# OPA_T12.net
KiCad netlist of a schematic drawn in Altium Designer
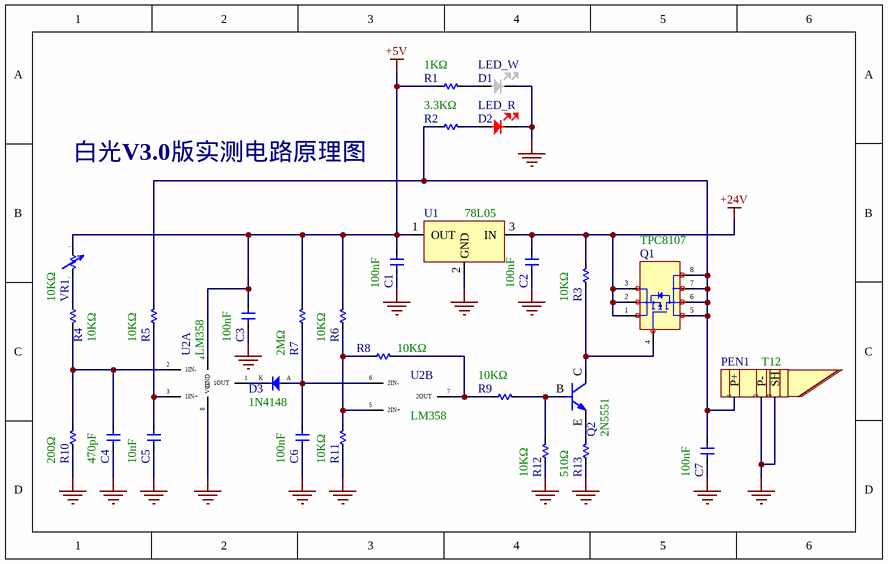
[diagram p0: OPA_T12.SchDoc]

(export (version "E")
  (design (tool "Eeschema 10.0.6"))
  (components
    (comp (ref "C1") (value "100nF") (description "贴片电容") (libsource (lib "SCHLIB_2022") (part "CAP NP")))
    (comp (ref "C2") (value "100nF") (description "贴片电容") (libsource (lib "SCHLIB_2022") (part "CAP NP")))
    (comp (ref "C3") (value "100nF") (description "贴片电容") (libsource (lib "SCHLIB_2022") (part "CAP NP")))
    (comp (ref "C4") (value "470pF") (description "贴片电容") (libsource (lib "SCHLIB_2022") (part "CAP NP")))
    (comp (ref "C5") (value "10nF") (description "贴片电容") (libsource (lib "SCHLIB_2022") (part "CAP NP")))
    (comp (ref "C6") (value "100nF") (description "贴片电容") (libsource (lib "SCHLIB_2022") (part "CAP NP")))
    (comp (ref "C7") (value "100nF") (description "贴片电容") (libsource (lib "SCHLIB_2022") (part "CAP NP")))
    (comp (ref "D1") (value "LED_W") (description "白色发光二极管") (libsource (lib "SCHLIB_2022") (part "LED_W")))
    (comp (ref "D2") (value "LED_R") (description "红色发光二极管") (libsource (lib "SCHLIB_2022") (part "LED_R")))
    (comp (ref "D3") (value "1N4148") (libsource (lib "SCHLIB_2022") (part "DIODE")))
    (comp (ref "PEN1") (value "T12") (footprint "T13") (libsource (lib "SCHLIB_2022") (part "IRON_PEN")))
    (comp (ref "Q1")
      (value "TPC8107")
      (footprint "SO-8M")
      (description "P沟道 40V 10A")
      (libsource (lib "SCHLIB_2022") (part "AO4485"))
    )
    (comp (ref "Q2") (value "2N5551") (libsource (lib "SCHLIB_2022") (part "NPN BCE")))
    (comp (ref "R1") (value "1KΩ") (description "贴片电阻") (libsource (lib "SCHLIB_2022") (part "ResSemi")))
    (comp (ref "R2") (value "3.3KΩ") (description "贴片电阻") (libsource (lib "SCHLIB_2022") (part "ResSemi")))
    (comp (ref "R3") (value "10KΩ") (description "贴片电阻") (libsource (lib "SCHLIB_2022") (part "ResSemi")))
    (comp (ref "R4") (value "10KΩ") (description "贴片电阻") (libsource (lib "SCHLIB_2022") (part "ResSemi")))
    (comp (ref "R5") (value "10KΩ") (description "贴片电阻") (libsource (lib "SCHLIB_2022") (part "ResSemi")))
    (comp (ref "R6") (value "10KΩ") (description "贴片电阻") (libsource (lib "SCHLIB_2022") (part "ResSemi")))
    (comp (ref "R7") (value "2MΩ") (description "贴片电阻") (libsource (lib "SCHLIB_2022") (part "ResSemi")))
    (comp (ref "R8") (value "10KΩ") (description "贴片电阻") (libsource (lib "SCHLIB_2022") (part "ResSemi")))
    (comp (ref "R9") (value "10KΩ") (description "贴片电阻") (libsource (lib "SCHLIB_2022") (part "ResSemi")))
    (comp (ref "R10") (value "200Ω") (description "贴片电阻") (libsource (lib "SCHLIB_2022") (part "ResSemi")))
    (comp (ref "R11") (value "10KΩ") (description "贴片电阻") (libsource (lib "SCHLIB_2022") (part "ResSemi")))
    (comp (ref "R12") (value "10KΩ") (description "贴片电阻") (libsource (lib "SCHLIB_2022") (part "ResSemi")))
    (comp (ref "R13") (value "510Ω") (description "贴片电阻") (libsource (lib "SCHLIB_2022") (part "ResSemi")))
    (comp (ref "U1")
      (value "78L05")
      (footprint "SOT-89")
      (description "5V线性稳压芯片")
      (libsource (lib "SCHLIB_2022") (part "78L05"))
    )
    (comp (ref "U2") (value "LM358") (footprint "SO-8") (libsource (lib "SCHLIB_2022") (part "LM393")))
    (comp (ref "VR1") (value "10KΩ") (libsource (lib "SCHLIB_2022") (part "ResSemi_5")))
  )
  (nets
    (net (code "1") (name "+5V") (class "Default")
      (node (ref "C1") (pin "1") (pinfunction "1_1") (pintype "passive"))
      (node (ref "C3") (pin "1") (pinfunction "1_1") (pintype "passive"))
      (node (ref "R1") (pin "1") (pinfunction "1_1") (pintype "passive"))
      (node (ref "R6") (pin "2") (pinfunction "2_2") (pintype "passive"))
      (node (ref "R7") (pin "2") (pinfunction "2_2") (pintype "passive"))
      (node (ref "U1") (pin "1") (pinfunction "OUT_1") (pintype "passive"))
      (node (ref "U2") (pin "4") (pinfunction "GND_4") (pintype "passive"))
      (node (ref "VR1") (pin "1") (pinfunction "1_1") (pintype "passive"))
    )
    (net (code "2") (name "+24V") (class "Default")
      (node (ref "C2") (pin "1") (pinfunction "1_1") (pintype "passive"))
      (node (ref "Q1") (pin "1") (pinfunction "S_1") (pintype "passive"))
      (node (ref "Q1") (pin "2") (pinfunction "S_2") (pintype "passive"))
      (node (ref "Q1") (pin "3") (pinfunction "S_3") (pintype "passive"))
      (node (ref "R3") (pin "2") (pinfunction "2_2") (pintype "passive"))
      (node (ref "U1") (pin "3") (pinfunction "IN_3") (pintype "passive"))
    )
    (net (code "3") (name "GND") (class "Default")
      (node (ref "C1") (pin "2") (pinfunction "2_2") (pintype "passive"))
      (node (ref "C2") (pin "2") (pinfunction "2_2") (pintype "passive"))
      (node (ref "C3") (pin "2") (pinfunction "2_2") (pintype "passive"))
      (node (ref "C4") (pin "2") (pinfunction "2_2") (pintype "passive"))
      (node (ref "C5") (pin "2") (pinfunction "2_2") (pintype "passive"))
      (node (ref "C6") (pin "2") (pinfunction "2_2") (pintype "passive"))
      (node (ref "C7") (pin "2") (pinfunction "2_2") (pintype "passive"))
      (node (ref "D1") (pin "C") (pinfunction "CATHODE_C") (pintype "passive"))
      (node (ref "D2") (pin "C") (pinfunction "CATHODE_C") (pintype "passive"))
      (node (ref "PEN1") (pin "2") (pinfunction "P-_2") (pintype "passive"))
      (node (ref "PEN1") (pin "3") (pinfunction "SH_3") (pintype "passive"))
      (node (ref "R10") (pin "1") (pinfunction "1_1") (pintype "passive"))
      (node (ref "R11") (pin "1") (pinfunction "1_1") (pintype "passive"))
      (node (ref "R12") (pin "1") (pinfunction "1_1") (pintype "passive"))
      (node (ref "R13") (pin "1") (pinfunction "1_1") (pintype "passive"))
      (node (ref "U1") (pin "2") (pinfunction "GND_2") (pintype "passive"))
      (node (ref "U2") (pin "8") (pinfunction "VCC_8") (pintype "passive"))
    )
    (net (code "4") (name "Net-(D1-ANODE)") (class "Default")
      (node (ref "D1") (pin "A") (pinfunction "ANODE_A") (pintype "passive"))
      (node (ref "R1") (pin "2") (pinfunction "2_2") (pintype "passive"))
    )
    (net (code "5") (name "Net-(D2-ANODE)") (class "Default")
      (node (ref "D2") (pin "A") (pinfunction "ANODE_A") (pintype "passive"))
      (node (ref "R2") (pin "2") (pinfunction "2_2") (pintype "passive"))
    )
    (net (code "6") (name "Net-(D3-ANODE)") (class "Default")
      (node (ref "C6") (pin "1") (pinfunction "1_1") (pintype "passive"))
      (node (ref "D3") (pin "A") (pinfunction "ANODE_A") (pintype "passive"))
      (node (ref "R7") (pin "1") (pinfunction "1_1") (pintype "passive"))
      (node (ref "U2") (pin "6") (pinfunction "2IN-_6") (pintype "passive"))
    )
    (net (code "7") (name "Net-(D3-CATHODE)") (class "Default")
      (node (ref "D3") (pin "K") (pinfunction "CATHODE_K") (pintype "passive"))
      (node (ref "U2") (pin "1") (pinfunction "1OUT_1") (pintype "passive"))
    )
    (net (code "8") (name "Net-(PEN1-P+)") (class "Default")
      (node (ref "C7") (pin "1") (pinfunction "1_1") (pintype "passive"))
      (node (ref "PEN1") (pin "1") (pinfunction "P+_1") (pintype "passive"))
      (node (ref "Q1") (pin "5") (pinfunction "D_5") (pintype "passive"))
      (node (ref "Q1") (pin "6") (pinfunction "D_6") (pintype "passive"))
      (node (ref "Q1") (pin "7") (pinfunction "D_7") (pintype "passive"))
      (node (ref "Q1") (pin "8") (pinfunction "D_8") (pintype "passive"))
      (node (ref "R2") (pin "1") (pinfunction "1_1") (pintype "passive"))
      (node (ref "R5") (pin "2") (pinfunction "2_2") (pintype "passive"))
    )
    (net (code "9") (name "Net-(Q1-G)") (class "Default")
      (node (ref "Q1") (pin "4") (pinfunction "G_4") (pintype "passive"))
      (node (ref "Q2") (pin "C") (pinfunction "COLLECTOR_C") (pintype "passive"))
      (node (ref "R3") (pin "1") (pinfunction "1_1") (pintype "passive"))
    )
    (net (code "10") (name "Net-(Q2-BASE)") (class "Default")
      (node (ref "Q2") (pin "B") (pinfunction "BASE_B") (pintype "passive"))
      (node (ref "R12") (pin "2") (pinfunction "2_2") (pintype "passive"))
      (node (ref "R9") (pin "2") (pinfunction "2_2") (pintype "passive"))
    )
    (net (code "11") (name "Net-(Q2-EMITTER)") (class "Default")
      (node (ref "Q2") (pin "E") (pinfunction "EMITTER_E") (pintype "passive"))
      (node (ref "R13") (pin "2") (pinfunction "2_2") (pintype "passive"))
    )
    (net (code "12") (name "Net-(R4-Pad1)") (class "Default")
      (node (ref "R4") (pin "1") (pinfunction "1_1") (pintype "passive"))
      (node (ref "VR1") (pin "2") (pinfunction "2_2") (pintype "passive"))
    )
    (net (code "13") (name "Net-(U2A-1IN+)") (class "Default")
      (node (ref "C5") (pin "1") (pinfunction "1_1") (pintype "passive"))
      (node (ref "R5") (pin "1") (pinfunction "1_1") (pintype "passive"))
      (node (ref "U2") (pin "3") (pinfunction "1IN+_3") (pintype "passive"))
    )
    (net (code "14") (name "Net-(U2A-1IN-)") (class "Default")
      (node (ref "C4") (pin "1") (pinfunction "1_1") (pintype "passive"))
      (node (ref "R10") (pin "2") (pinfunction "2_2") (pintype "passive"))
      (node (ref "R4") (pin "2") (pinfunction "2_2") (pintype "passive"))
      (node (ref "U2") (pin "2") (pinfunction "1IN-_2") (pintype "passive"))
    )
    (net (code "15") (name "Net-(U2B-2IN+)") (class "Default")
      (node (ref "R11") (pin "2") (pinfunction "2_2") (pintype "passive"))
      (node (ref "R6") (pin "1") (pinfunction "1_1") (pintype "passive"))
      (node (ref "R8") (pin "1") (pinfunction "1_1") (pintype "passive"))
      (node (ref "U2") (pin "5") (pinfunction "2IN+_5") (pintype "passive"))
    )
    (net (code "16") (name "Net-(U2B-2OUT)") (class "Default")
      (node (ref "R8") (pin "2") (pinfunction "2_2") (pintype "passive"))
      (node (ref "R9") (pin "1") (pinfunction "1_1") (pintype "passive"))
      (node (ref "U2") (pin "7") (pinfunction "2OUT_7") (pintype "passive"))
    )
  )
)
